# 20x20_adapter_rush_v3.net
KiCad netlist of a schematic drawn in EAGLE
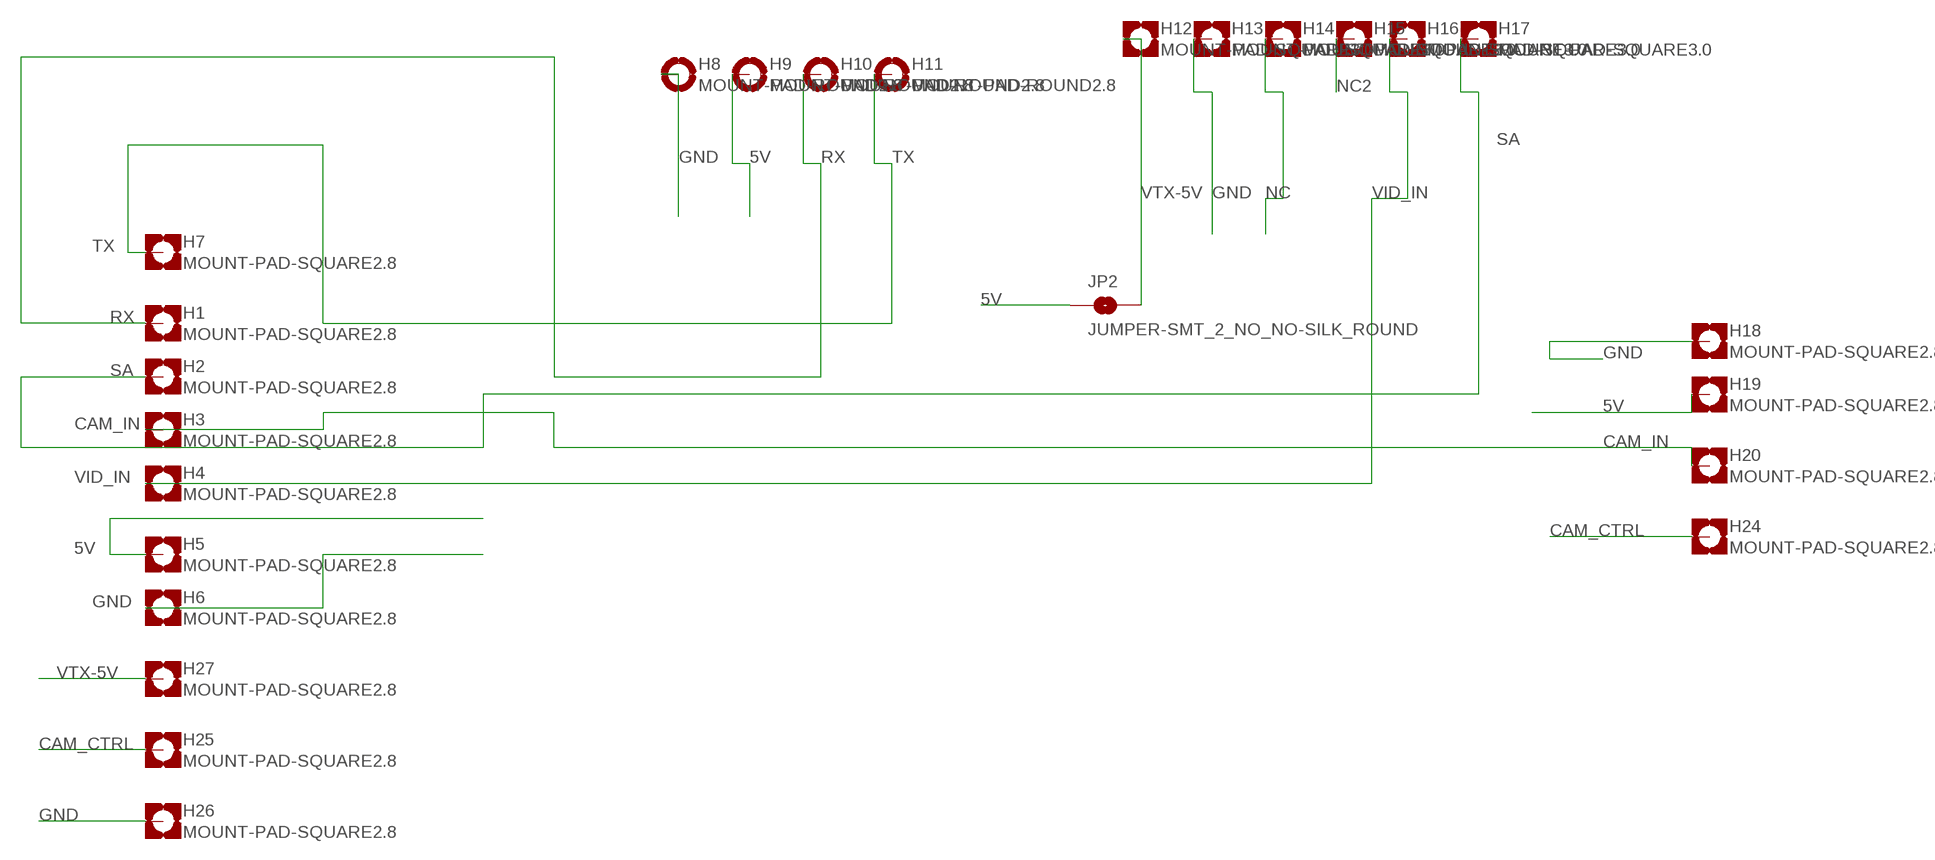
[diagram p0: schematic, sheet 1]

(export (version "E")
  (design (tool "Eeschema 10.0.6"))
  (components
    (comp (ref "H1")
      (value "MOUNT-PAD-SQUARE2.8")
      (footprint "eagle-import:2,8-PAD-SQUARE")
      (libsource (lib "eagle-import") (part "MOUNT-PAD-SQUARE2.8"))
    )
    (comp (ref "H2")
      (value "MOUNT-PAD-SQUARE2.8")
      (footprint "eagle-import:2,8-PAD-SQUARE")
      (libsource (lib "eagle-import") (part "MOUNT-PAD-SQUARE2.8"))
    )
    (comp (ref "H3")
      (value "MOUNT-PAD-SQUARE2.8")
      (footprint "eagle-import:2,8-PAD-SQUARE")
      (libsource (lib "eagle-import") (part "MOUNT-PAD-SQUARE2.8"))
    )
    (comp (ref "H4")
      (value "MOUNT-PAD-SQUARE2.8")
      (footprint "eagle-import:2,8-PAD-SQUARE")
      (libsource (lib "eagle-import") (part "MOUNT-PAD-SQUARE2.8"))
    )
    (comp (ref "H5")
      (value "MOUNT-PAD-SQUARE2.8")
      (footprint "eagle-import:2,8-PAD-SQUARE")
      (libsource (lib "eagle-import") (part "MOUNT-PAD-SQUARE2.8"))
    )
    (comp (ref "H6")
      (value "MOUNT-PAD-SQUARE2.8")
      (footprint "eagle-import:2,8-PAD-SQUARE")
      (libsource (lib "eagle-import") (part "MOUNT-PAD-SQUARE2.8"))
    )
    (comp (ref "H7")
      (value "MOUNT-PAD-SQUARE2.8")
      (footprint "eagle-import:2,8-PAD-SQUARE")
      (libsource (lib "eagle-import") (part "MOUNT-PAD-SQUARE2.8"))
    )
    (comp (ref "H8")
      (value "MOUNT-PAD-ROUND2.8")
      (footprint "eagle-import:1,0-PAD")
      (libsource (lib "eagle-import") (part "MOUNT-PAD-ROUND2.8"))
    )
    (comp (ref "H9")
      (value "MOUNT-PAD-ROUND2.8")
      (footprint "eagle-import:1,0-PAD")
      (libsource (lib "eagle-import") (part "MOUNT-PAD-ROUND2.8"))
    )
    (comp (ref "H10")
      (value "MOUNT-PAD-ROUND2.8")
      (footprint "eagle-import:1,0-PAD")
      (libsource (lib "eagle-import") (part "MOUNT-PAD-ROUND2.8"))
    )
    (comp (ref "H11")
      (value "MOUNT-PAD-ROUND2.8")
      (footprint "eagle-import:1,0-PAD")
      (libsource (lib "eagle-import") (part "MOUNT-PAD-ROUND2.8"))
    )
    (comp (ref "H12")
      (value "MOUNT-PAD-SQUARE3.0")
      (footprint "eagle-import:1,5-PAD-SQUARE")
      (libsource (lib "eagle-import") (part "MOUNT-PAD-SQUARE3.0"))
    )
    (comp (ref "H13")
      (value "MOUNT-PAD-SQUARE3.0")
      (footprint "eagle-import:1,5-PAD-SQUARE")
      (libsource (lib "eagle-import") (part "MOUNT-PAD-SQUARE3.0"))
    )
    (comp (ref "H14")
      (value "MOUNT-PAD-SQUARE3.0")
      (footprint "eagle-import:1,5-PAD-SQUARE")
      (libsource (lib "eagle-import") (part "MOUNT-PAD-SQUARE3.0"))
    )
    (comp (ref "H15")
      (value "MOUNT-PAD-SQUARE3.0")
      (footprint "eagle-import:1,5-PAD-SQUARE")
      (libsource (lib "eagle-import") (part "MOUNT-PAD-SQUARE3.0"))
    )
    (comp (ref "H16")
      (value "MOUNT-PAD-SQUARE3.0")
      (footprint "eagle-import:1,5-PAD-SQUARE")
      (libsource (lib "eagle-import") (part "MOUNT-PAD-SQUARE3.0"))
    )
    (comp (ref "H17")
      (value "MOUNT-PAD-SQUARE3.0")
      (footprint "eagle-import:1,5-PAD-SQUARE")
      (libsource (lib "eagle-import") (part "MOUNT-PAD-SQUARE3.0"))
    )
    (comp (ref "H18")
      (value "MOUNT-PAD-SQUARE2.8")
      (footprint "eagle-import:2,8-PAD-SQUARE")
      (libsource (lib "eagle-import") (part "MOUNT-PAD-SQUARE2.8"))
    )
    (comp (ref "H19")
      (value "MOUNT-PAD-SQUARE2.8")
      (footprint "eagle-import:2,8-PAD-SQUARE")
      (libsource (lib "eagle-import") (part "MOUNT-PAD-SQUARE2.8"))
    )
    (comp (ref "H20")
      (value "MOUNT-PAD-SQUARE2.8")
      (footprint "eagle-import:2,8-PAD-SQUARE")
      (libsource (lib "eagle-import") (part "MOUNT-PAD-SQUARE2.8"))
    )
    (comp (ref "H24")
      (value "MOUNT-PAD-SQUARE2.8")
      (footprint "eagle-import:2,8-PAD-SQUARE")
      (libsource (lib "eagle-import") (part "MOUNT-PAD-SQUARE2.8"))
    )
    (comp (ref "H25")
      (value "MOUNT-PAD-SQUARE2.8")
      (footprint "eagle-import:2,8-PAD-SQUARE")
      (libsource (lib "eagle-import") (part "MOUNT-PAD-SQUARE2.8"))
    )
    (comp (ref "H26")
      (value "MOUNT-PAD-SQUARE2.8")
      (footprint "eagle-import:2,8-PAD-SQUARE")
      (libsource (lib "eagle-import") (part "MOUNT-PAD-SQUARE2.8"))
    )
    (comp (ref "H27")
      (value "MOUNT-PAD-SQUARE2.8")
      (footprint "eagle-import:2,8-PAD-SQUARE")
      (libsource (lib "eagle-import") (part "MOUNT-PAD-SQUARE2.8"))
    )
    (comp (ref "JP2")
      (value "JUMPER-SMT_2_NO_NO-SILK_ROUND")
      (footprint "eagle-import:SMT-JUMPER_2_NO_NO-SILK_ROUND")
      (libsource (lib "eagle-import") (part "JUMPER-SMT_2_NO_NO-SILK_ROUND"))
    )
  )
  (nets
    (net (code "1") (name "/5V") (class "Default")
      (node (ref "H19") (pin "P$2") (pinfunction "MOUNT_P$2") (pintype "passive"))
      (node (ref "H5") (pin "P$2") (pinfunction "MOUNT_P$2") (pintype "passive"))
      (node (ref "H9") (pin "B1,0") (pinfunction "MOUNT_B1,0") (pintype "passive"))
      (node (ref "JP2") (pin "1") (pinfunction "1_1") (pintype "passive"))
    )
    (net (code "2") (name "/CAM_CTRL") (class "Default")
      (node (ref "H24") (pin "P$2") (pinfunction "MOUNT_P$2") (pintype "passive"))
      (node (ref "H25") (pin "P$2") (pinfunction "MOUNT_P$2") (pintype "passive"))
    )
    (net (code "3") (name "/CAM_IN") (class "Default")
      (node (ref "H20") (pin "P$2") (pinfunction "MOUNT_P$2") (pintype "passive"))
      (node (ref "H3") (pin "P$2") (pinfunction "MOUNT_P$2") (pintype "passive"))
    )
    (net (code "4") (name "/GND") (class "Default")
      (node (ref "H13") (pin "P$1") (pinfunction "MOUNT_P$1") (pintype "passive"))
      (node (ref "H18") (pin "P$2") (pinfunction "MOUNT_P$2") (pintype "passive"))
      (node (ref "H26") (pin "P$2") (pinfunction "MOUNT_P$2") (pintype "passive"))
      (node (ref "H6") (pin "P$2") (pinfunction "MOUNT_P$2") (pintype "passive"))
      (node (ref "H8") (pin "B1,0") (pinfunction "MOUNT_B1,0") (pintype "passive"))
    )
    (net (code "5") (name "/NC") (class "Default")
      (node (ref "H14") (pin "P$1") (pinfunction "MOUNT_P$1") (pintype "passive"))
    )
    (net (code "6") (name "/NC2") (class "Default")
      (node (ref "H15") (pin "P$1") (pinfunction "MOUNT_P$1") (pintype "passive"))
    )
    (net (code "7") (name "/RX") (class "Default")
      (node (ref "H1") (pin "P$2") (pinfunction "MOUNT_P$2") (pintype "passive"))
      (node (ref "H10") (pin "B1,0") (pinfunction "MOUNT_B1,0") (pintype "passive"))
    )
    (net (code "8") (name "/SA") (class "Default")
      (node (ref "H17") (pin "P$1") (pinfunction "MOUNT_P$1") (pintype "passive"))
      (node (ref "H2") (pin "P$2") (pinfunction "MOUNT_P$2") (pintype "passive"))
    )
    (net (code "9") (name "/TX") (class "Default")
      (node (ref "H11") (pin "B1,0") (pinfunction "MOUNT_B1,0") (pintype "passive"))
      (node (ref "H7") (pin "P$2") (pinfunction "MOUNT_P$2") (pintype "passive"))
    )
    (net (code "10") (name "/VID_IN") (class "Default")
      (node (ref "H16") (pin "P$1") (pinfunction "MOUNT_P$1") (pintype "passive"))
      (node (ref "H4") (pin "P$2") (pinfunction "MOUNT_P$2") (pintype "passive"))
    )
    (net (code "11") (name "/VTX-5V") (class "Default")
      (node (ref "H12") (pin "P$1") (pinfunction "MOUNT_P$1") (pintype "passive"))
      (node (ref "H27") (pin "P$2") (pinfunction "MOUNT_P$2") (pintype "passive"))
      (node (ref "JP2") (pin "2") (pinfunction "2_2") (pintype "passive"))
    )
  )
)
